# Shutdown_Circuit.net
KiCad netlist of a schematic drawn in Altium Designer
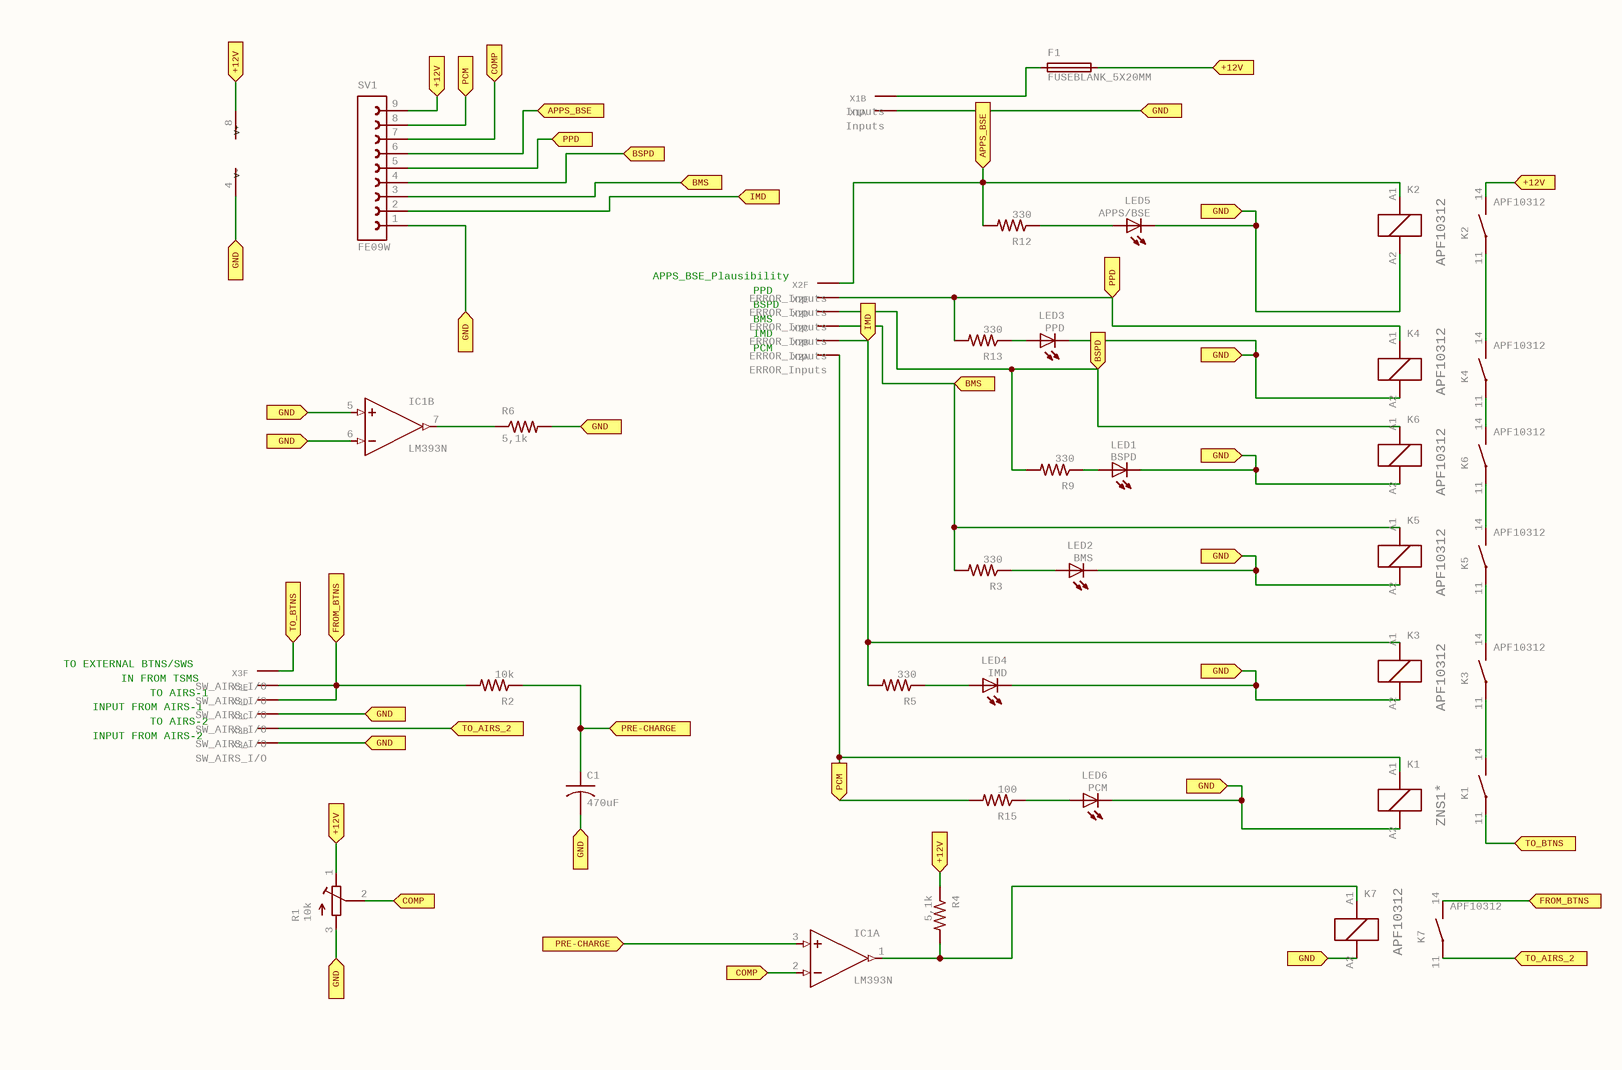
[diagram p0: Shutdown Circuit.SchDoc]

(export (version "E")
  (design (tool "Eeschema 10.0.6"))
  (components
    (comp (ref "APPS/BSE")
      (value "LED5")
      (footprint "LED3MM")
      (fields (field (name "MF") "MF") (field (name "MPN") "MPN"))
      (libsource (lib "led") (part "LED3MM"))
    )
    (comp (ref "BMS")
      (value "LED2")
      (footprint "LED3MM")
      (fields (field (name "MF") "MF") (field (name "MPN") "MPN"))
      (libsource (lib "led") (part "LED3MM"))
    )
    (comp (ref "BSPD")
      (value "LED1")
      (footprint "LED3MM")
      (fields (field (name "MF") "MF") (field (name "MPN") "MPN"))
      (libsource (lib "led") (part "LED3MM"))
    )
    (comp (ref "C1")
      (value "470uF")
      (footprint "C050-045X075")
      (description "CAPACITOR, American symbol")
      (fields (field (name "MF") "MF") (field (name "MPN") "MPN"))
      (libsource (lib "resistor") (part "C-US050-045X075"))
    )
    (comp (ref "F1")
      (value "FUSEBLANK_5X20MM")
      (footprint "FUSE_HOLDER_5X20MM")
      (description "Fuse")
      (fields (field (name "MF") "MF") (field (name "MPN") "MPN"))
      (libsource (lib "fuse") (part "FUSEBLANK_5X20MM"))
    )
    (comp (ref "IC1")
      (value "LM393N")
      (footprint "DIL08")
      (description "COMPARATOR")
      (fields
        (field (name "V+") "V+")
        (field (name "V-") "V-")
        (field (name "MF") "MF")
        (field (name "MPN") "MPN")
      )
      (libsource (lib "linear") (part "LM393N"))
    )
    (comp (ref "IMD")
      (value "LED4")
      (footprint "LED3MM")
      (fields (field (name "MF") "MF") (field (name "MPN") "MPN"))
      (libsource (lib "led") (part "LED3MM"))
    )
    (comp (ref "K1")
      (value "ZNS1*")
      (footprint "ZN1")
      (description "Miniature Power PCB Relay SCHRACK   1pole 10 A Source: http://www.schrack.com/.. 5847.pdf")
      (fields (field (name "PART") "K1") (field (name "MF") "MF") (field (name "MPN") "MPN"))
      (libsource (lib "relay") (part "ZNS1*"))
    )
    (comp (ref "K2")
      (value "APF10312")
      (footprint "SNR-V1")
      (description "Slim PCB Relay 1 pole 6 A SCHRACK   Source: http://www.schrack.com/.. 5815.pdf")
      (fields (field (name "PART") "K2") (field (name "MF") "MF") (field (name "MPN") "MPN"))
      (libsource (lib "relay") (part "SN*R1"))
    )
    (comp (ref "K3")
      (value "APF10312")
      (footprint "SNR-V1")
      (description "Slim PCB Relay 1 pole 6 A SCHRACK   Source: http://www.schrack.com/.. 5815.pdf")
      (fields (field (name "PART") "K3") (field (name "MF") "MF") (field (name "MPN") "MPN"))
      (libsource (lib "relay") (part "SN*R1"))
    )
    (comp (ref "K4")
      (value "APF10312")
      (footprint "SNR-V1")
      (description "Slim PCB Relay 1 pole 6 A SCHRACK   Source: http://www.schrack.com/.. 5815.pdf")
      (fields (field (name "PART") "K4") (field (name "MF") "MF") (field (name "MPN") "MPN"))
      (libsource (lib "relay") (part "SN*R1"))
    )
    (comp (ref "K5")
      (value "APF10312")
      (footprint "SNR-V1")
      (description "Slim PCB Relay 1 pole 6 A SCHRACK   Source: http://www.schrack.com/.. 5815.pdf")
      (fields (field (name "PART") "K5") (field (name "MF") "MF") (field (name "MPN") "MPN"))
      (libsource (lib "relay") (part "SN*R1"))
    )
    (comp (ref "K6")
      (value "APF10312")
      (footprint "SNR-V1")
      (description "Slim PCB Relay 1 pole 6 A SCHRACK   Source: http://www.schrack.com/.. 5815.pdf")
      (fields (field (name "PART") "K6") (field (name "MF") "MF") (field (name "MPN") "MPN"))
      (libsource (lib "relay") (part "SN*R1"))
    )
    (comp (ref "K7")
      (value "APF10312")
      (footprint "SNR-V1")
      (description "Slim PCB Relay 1 pole 6 A SCHRACK   Source: http://www.schrack.com/.. 5815.pdf")
      (fields (field (name "PART") "K7") (field (name "MF") "MF") (field (name "MPN") "MPN"))
      (libsource (lib "relay") (part "SN*R1"))
    )
    (comp (ref "PCM")
      (value "LED6")
      (footprint "LED3MM")
      (fields (field (name "MF") "MF") (field (name "MPN") "MPN"))
      (libsource (lib "led") (part "LED3MM"))
    )
    (comp (ref "PPD")
      (value "LED3")
      (footprint "LED3MM")
      (fields (field (name "MF") "MF") (field (name "MPN") "MPN"))
      (libsource (lib "led") (part "LED3MM"))
    )
    (comp (ref "R1")
      (value "10k")
      (footprint "RTRIM43P")
      (description "Trimm resistor")
      (fields (field (name "MF") "MF") (field (name "MPN") "MPN"))
      (libsource (lib "rcl") (part "R-TRIMM43P"))
    )
    (comp (ref "R2")
      (value "10k")
      (footprint "0207/10")
      (description "RESISTOR, American symbol")
      (fields (field (name "MF") "MF") (field (name "MPN") "MPN"))
      (libsource (lib "resistor") (part "R-US_0207/10"))
    )
    (comp (ref "R3")
      (value "330")
      (footprint "0207/10")
      (description "RESISTOR, American symbol")
      (fields (field (name "MF") "MF") (field (name "MPN") "MPN"))
      (libsource (lib "resistor") (part "R-US_0207/10"))
    )
    (comp (ref "R4")
      (value "5,1k")
      (footprint "0207/10")
      (description "RESISTOR, American symbol")
      (fields (field (name "MF") "MF") (field (name "MPN") "MPN"))
      (libsource (lib "resistor") (part "R-US_0207/10"))
    )
    (comp (ref "R5")
      (value "330")
      (footprint "0207/10")
      (description "RESISTOR, American symbol")
      (fields (field (name "MF") "MF") (field (name "MPN") "MPN"))
      (libsource (lib "resistor") (part "R-US_0207/10"))
    )
    (comp (ref "R6")
      (value "5,1k")
      (footprint "0207/10")
      (description "RESISTOR, American symbol")
      (fields (field (name "MF") "MF") (field (name "MPN") "MPN"))
      (libsource (lib "resistor") (part "R-US_0207/10"))
    )
    (comp (ref "R9")
      (value "330")
      (footprint "0207/10")
      (description "RESISTOR, American symbol")
      (fields (field (name "MF") "MF") (field (name "MPN") "MPN"))
      (libsource (lib "resistor") (part "R-US_0207/10"))
    )
    (comp (ref "R12")
      (value "330")
      (footprint "0207/10")
      (description "RESISTOR, American symbol")
      (fields (field (name "MF") "MF") (field (name "MPN") "MPN"))
      (libsource (lib "resistor") (part "R-US_0207/10"))
    )
    (comp (ref "R13")
      (value "330")
      (footprint "0207/10")
      (description "RESISTOR, American symbol")
      (fields (field (name "MF") "MF") (field (name "MPN") "MPN"))
      (libsource (lib "resistor") (part "R-US_0207/10"))
    )
    (comp (ref "R15")
      (value "100")
      (footprint "0207/10")
      (description "RESISTOR, American symbol")
      (fields (field (name "MF") "MF") (field (name "MPN") "MPN"))
      (libsource (lib "resistor") (part "R-US_0207/10"))
    )
    (comp (ref "SV1")
      (value "FE09W")
      (footprint "FE09W")
      (description "FEMALE HEADER")
      (fields (field (name "MF") "MF") (field (name "MPN") "MPN") (field (name "LIBRARYNAME") "con-lsta"))
      (libsource (lib "con-lsta") (part "FE09W"))
    )
    (comp (ref "X1")
      (value "Inputs")
      (footprint "22-23-2021")
      (description ".100\" (2.54mm) Center Header - 2 Pin")
      (fields (field (name "MF") "MOLEX") (field (name "MPN") "22-23-2021"))
      (libsource (lib "con-molex") (part "22-23-2021"))
    )
    (comp (ref "X2")
      (value "ERROR_Inputs")
      (footprint "22-23-2061")
      (description ".100\" (2.54mm) Center Header - 6 Pin")
      (fields (field (name "MF") "MOLEX") (field (name "MPN") "22-23-2061"))
      (libsource (lib "con-molex") (part "22-23-2061"))
    )
    (comp (ref "X3")
      (value "SW_AIRS_I/O")
      (footprint "22-23-2061")
      (description ".100\" (2.54mm) Center Header - 6 Pin")
      (fields (field (name "MF") "MOLEX") (field (name "MPN") "22-23-2061"))
      (libsource (lib "con-molex") (part "22-23-2061"))
    )
  )
  (nets
    (net (code "1") (name "/+12V") (class "Default")
      (node (ref "F1") (pin "2") (pinfunction "2_2") (pintype "passive"))
      (node (ref "IC1") (pin "8") (pinfunction "V+_8") (pintype "power_in"))
      (node (ref "K2") (pin "14") (pinfunction "S_14") (pintype "passive"))
      (node (ref "R1") (pin "1") (pinfunction "E_1") (pintype "passive"))
      (node (ref "R4") (pin "1") (pinfunction "1_1") (pintype "passive"))
      (node (ref "SV1") (pin "9") (pinfunction "9_9") (pintype "passive"))
    )
    (net (code "2") (name "/APPS_BSE") (class "Default")
      (node (ref "K2") (pin "A1") (pinfunction "1_A1") (pintype "passive"))
      (node (ref "R12") (pin "2") (pinfunction "2_2") (pintype "passive"))
      (node (ref "SV1") (pin "6") (pinfunction "6_6") (pintype "passive"))
      (node (ref "X2") (pin "6") (pinfunction "S_6") (pintype "passive"))
    )
    (net (code "3") (name "/BMS") (class "Default")
      (node (ref "K5") (pin "A1") (pinfunction "1_A1") (pintype "passive"))
      (node (ref "R3") (pin "2") (pinfunction "2_2") (pintype "passive"))
      (node (ref "SV1") (pin "3") (pinfunction "3_3") (pintype "passive"))
      (node (ref "X2") (pin "3") (pinfunction "S_3") (pintype "passive"))
    )
    (net (code "4") (name "/BSPD") (class "Default")
      (node (ref "K6") (pin "A1") (pinfunction "1_A1") (pintype "passive"))
      (node (ref "R9") (pin "2") (pinfunction "2_2") (pintype "passive"))
      (node (ref "SV1") (pin "4") (pinfunction "4_4") (pintype "passive"))
      (node (ref "X2") (pin "4") (pinfunction "S_4") (pintype "passive"))
    )
    (net (code "5") (name "/COMP") (class "Default")
      (node (ref "IC1") (pin "2") (pinfunction "-IN_2") (pintype "input"))
      (node (ref "R1") (pin "2") (pinfunction "S_2") (pintype "passive"))
      (node (ref "SV1") (pin "7") (pinfunction "7_7") (pintype "passive"))
    )
    (net (code "6") (name "/FROM_BTNS") (class "Default")
      (node (ref "K7") (pin "14") (pinfunction "S_14") (pintype "passive"))
      (node (ref "R2") (pin "2") (pinfunction "2_2") (pintype "passive"))
      (node (ref "X3") (pin "4") (pinfunction "S_4") (pintype "passive"))
      (node (ref "X3") (pin "5") (pinfunction "S_5") (pintype "passive"))
    )
    (net (code "7") (name "/GND") (class "Default")
      (node (ref "APPS/BSE") (pin "K") (pinfunction "C_K") (pintype "passive"))
      (node (ref "BMS") (pin "K") (pinfunction "C_K") (pintype "passive"))
      (node (ref "BSPD") (pin "K") (pinfunction "C_K") (pintype "passive"))
      (node (ref "C1") (pin "2") (pinfunction "2_2") (pintype "passive"))
      (node (ref "IC1") (pin "4") (pinfunction "V-_4") (pintype "power_in"))
      (node (ref "IC1") (pin "5") (pinfunction "+IN_5") (pintype "input"))
      (node (ref "IC1") (pin "6") (pinfunction "-IN_6") (pintype "input"))
      (node (ref "IMD") (pin "K") (pinfunction "C_K") (pintype "passive"))
      (node (ref "K1") (pin "A2") (pinfunction "2_A2") (pintype "passive"))
      (node (ref "K2") (pin "A2") (pinfunction "2_A2") (pintype "passive"))
      (node (ref "K3") (pin "A2") (pinfunction "2_A2") (pintype "passive"))
      (node (ref "K4") (pin "A2") (pinfunction "2_A2") (pintype "passive"))
      (node (ref "K5") (pin "A2") (pinfunction "2_A2") (pintype "passive"))
      (node (ref "K6") (pin "A2") (pinfunction "2_A2") (pintype "passive"))
      (node (ref "K7") (pin "A2") (pinfunction "2_A2") (pintype "passive"))
      (node (ref "PCM") (pin "K") (pinfunction "C_K") (pintype "passive"))
      (node (ref "PPD") (pin "K") (pinfunction "C_K") (pintype "passive"))
      (node (ref "R1") (pin "3") (pinfunction "A_3") (pintype "passive"))
      (node (ref "R6") (pin "2") (pinfunction "2_2") (pintype "passive"))
      (node (ref "SV1") (pin "1") (pinfunction "1_1") (pintype "passive"))
      (node (ref "X1") (pin "1") (pinfunction "S_1") (pintype "passive"))
      (node (ref "X3") (pin "1") (pinfunction "S_1") (pintype "passive"))
      (node (ref "X3") (pin "3") (pinfunction "S_3") (pintype "passive"))
    )
    (net (code "8") (name "/IMD") (class "Default")
      (node (ref "K3") (pin "A1") (pinfunction "1_A1") (pintype "passive"))
      (node (ref "R5") (pin "2") (pinfunction "2_2") (pintype "passive"))
      (node (ref "SV1") (pin "2") (pinfunction "2_2") (pintype "passive"))
      (node (ref "X2") (pin "2") (pinfunction "S_2") (pintype "passive"))
    )
    (net (code "9") (name "/PCM") (class "Default")
      (node (ref "K1") (pin "A1") (pinfunction "1_A1") (pintype "passive"))
      (node (ref "R15") (pin "2") (pinfunction "2_2") (pintype "passive"))
      (node (ref "SV1") (pin "8") (pinfunction "8_8") (pintype "passive"))
      (node (ref "X2") (pin "1") (pinfunction "S_1") (pintype "passive"))
    )
    (net (code "10") (name "/PPD") (class "Default")
      (node (ref "K4") (pin "A1") (pinfunction "1_A1") (pintype "passive"))
      (node (ref "R13") (pin "2") (pinfunction "2_2") (pintype "passive"))
      (node (ref "SV1") (pin "5") (pinfunction "5_5") (pintype "passive"))
      (node (ref "X2") (pin "5") (pinfunction "S_5") (pintype "passive"))
    )
    (net (code "11") (name "/PRE-CHARGE") (class "Default")
      (node (ref "C1") (pin "1") (pinfunction "1_1") (pintype "passive"))
      (node (ref "IC1") (pin "3") (pinfunction "+IN_3") (pintype "input"))
      (node (ref "R2") (pin "1") (pinfunction "1_1") (pintype "passive"))
    )
    (net (code "12") (name "/TO_AIRS_2") (class "Default")
      (node (ref "K7") (pin "11") (pinfunction "P_11") (pintype "passive"))
      (node (ref "X3") (pin "2") (pinfunction "S_2") (pintype "passive"))
    )
    (net (code "13") (name "/TO_BTNS") (class "Default")
      (node (ref "K1") (pin "11") (pinfunction "P_11") (pintype "passive"))
      (node (ref "X3") (pin "6") (pinfunction "S_6") (pintype "passive"))
    )
    (net (code "14") (name "Net-(APPS/BSE-PadA)") (class "Default")
      (node (ref "APPS/BSE") (pin "A") (pinfunction "A_A") (pintype "passive"))
      (node (ref "R12") (pin "1") (pinfunction "1_1") (pintype "passive"))
    )
    (net (code "15") (name "Net-(BMS-PadA)") (class "Default")
      (node (ref "BMS") (pin "A") (pinfunction "A_A") (pintype "passive"))
      (node (ref "R3") (pin "1") (pinfunction "1_1") (pintype "passive"))
    )
    (net (code "16") (name "Net-(BSPD-PadA)") (class "Default")
      (node (ref "BSPD") (pin "A") (pinfunction "A_A") (pintype "passive"))
      (node (ref "R9") (pin "1") (pinfunction "1_1") (pintype "passive"))
    )
    (net (code "17") (name "Net-(IC1A-OUT)") (class "Default")
      (node (ref "IC1") (pin "1") (pinfunction "OUT_1") (pintype "output"))
      (node (ref "K7") (pin "A1") (pinfunction "1_A1") (pintype "passive"))
      (node (ref "R4") (pin "2") (pinfunction "2_2") (pintype "passive"))
    )
    (net (code "18") (name "Net-(IC1B-OUT)") (class "Default")
      (node (ref "IC1") (pin "7") (pinfunction "OUT_7") (pintype "output"))
      (node (ref "R6") (pin "1") (pinfunction "1_1") (pintype "passive"))
    )
    (net (code "19") (name "Net-(IMD-PadA)") (class "Default")
      (node (ref "IMD") (pin "A") (pinfunction "A_A") (pintype "passive"))
      (node (ref "R5") (pin "1") (pinfunction "1_1") (pintype "passive"))
    )
    (net (code "20") (name "Net-(K1B-S)") (class "Default")
      (node (ref "K1") (pin "14") (pinfunction "S_14") (pintype "passive"))
      (node (ref "K3") (pin "11") (pinfunction "P_11") (pintype "passive"))
    )
    (net (code "21") (name "Net-(K2B-P)") (class "Default")
      (node (ref "K2") (pin "11") (pinfunction "P_11") (pintype "passive"))
      (node (ref "K4") (pin "14") (pinfunction "S_14") (pintype "passive"))
    )
    (net (code "22") (name "Net-(K3B-S)") (class "Default")
      (node (ref "K3") (pin "14") (pinfunction "S_14") (pintype "passive"))
      (node (ref "K5") (pin "11") (pinfunction "P_11") (pintype "passive"))
    )
    (net (code "23") (name "Net-(K4B-P)") (class "Default")
      (node (ref "K4") (pin "11") (pinfunction "P_11") (pintype "passive"))
      (node (ref "K6") (pin "14") (pinfunction "S_14") (pintype "passive"))
    )
    (net (code "24") (name "Net-(K5B-S)") (class "Default")
      (node (ref "K5") (pin "14") (pinfunction "S_14") (pintype "passive"))
      (node (ref "K6") (pin "11") (pinfunction "P_11") (pintype "passive"))
    )
    (net (code "25") (name "Net-(PCM-PadA)") (class "Default")
      (node (ref "PCM") (pin "A") (pinfunction "A_A") (pintype "passive"))
      (node (ref "R15") (pin "1") (pinfunction "1_1") (pintype "passive"))
    )
    (net (code "26") (name "Net-(PPD-PadA)") (class "Default")
      (node (ref "PPD") (pin "A") (pinfunction "A_A") (pintype "passive"))
      (node (ref "R13") (pin "1") (pinfunction "1_1") (pintype "passive"))
    )
    (net (code "27") (name "Net-(X1B-S)") (class "Default")
      (node (ref "F1") (pin "1") (pinfunction "1_1") (pintype "passive"))
      (node (ref "X1") (pin "2") (pinfunction "S_2") (pintype "passive"))
    )
  )
)
